# moshimoshi-audio-v2.net
KiCad netlist of a schematic drawn in EAGLE
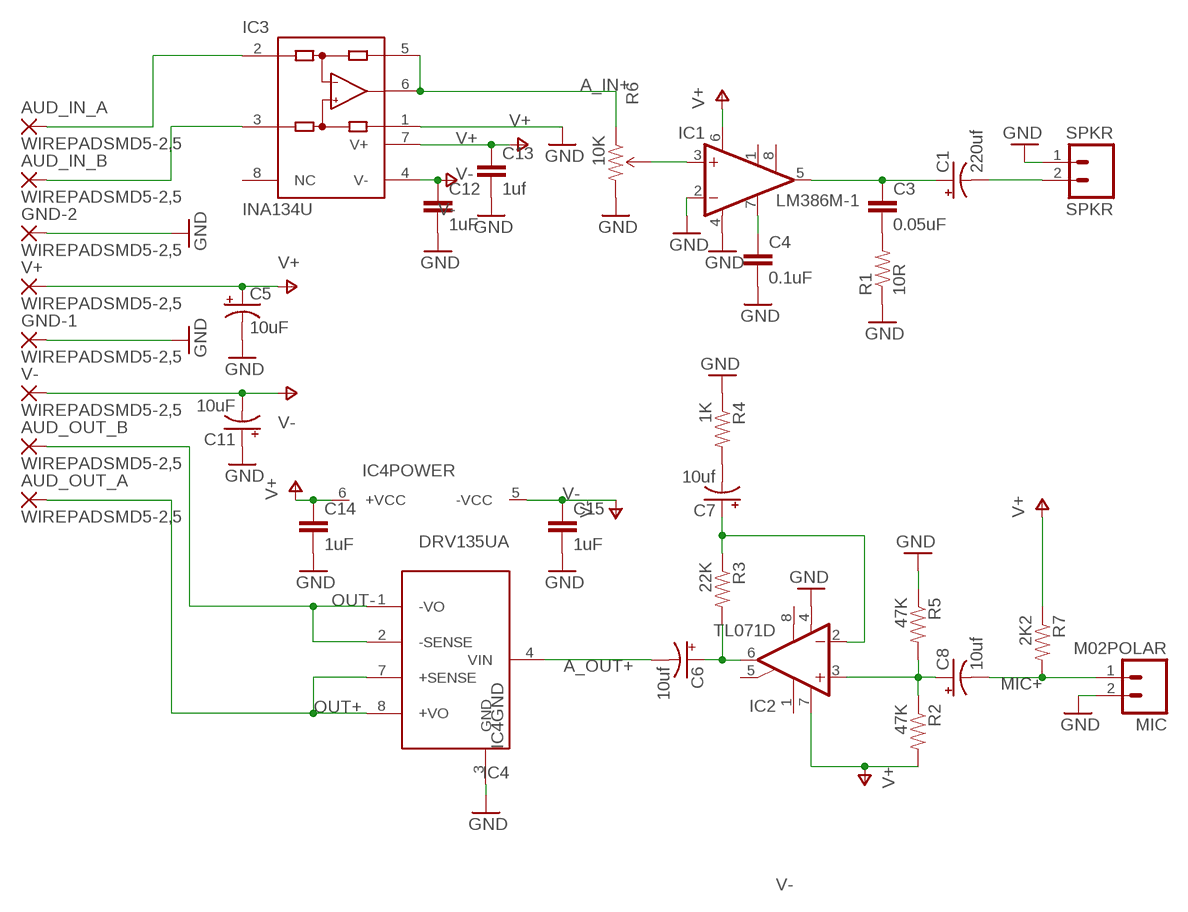
[diagram p0: schematic, sheet 1]

(export (version "E")
  (design (tool "Eeschema 10.0.6"))
  (components
    (comp (ref "AUD_IN_A")
      (value "WIREPADSMD5-2,5")
      (footprint "eagle-import:5-2,5")
      (libsource (lib "eagle-import") (part "WIREPADSMD5-2,5"))
    )
    (comp (ref "AUD_IN_B")
      (value "WIREPADSMD5-2,5")
      (footprint "eagle-import:5-2,5")
      (libsource (lib "eagle-import") (part "WIREPADSMD5-2,5"))
    )
    (comp (ref "AUD_OUT_A")
      (value "WIREPADSMD5-2,5")
      (footprint "eagle-import:5-2,5")
      (libsource (lib "eagle-import") (part "WIREPADSMD5-2,5"))
    )
    (comp (ref "AUD_OUT_B")
      (value "WIREPADSMD5-2,5")
      (footprint "eagle-import:5-2,5")
      (libsource (lib "eagle-import") (part "WIREPADSMD5-2,5"))
    )
    (comp (ref "C1")
      (value "220uf")
      (footprint "eagle-import:CPOL-RADIAL-100UF-25V")
      (libsource (lib "eagle-import") (part "CAP_POLPTH1"))
    )
    (comp (ref "C3")
      (value "0.05uF")
      (footprint "eagle-import:0805")
      (libsource (lib "eagle-import") (part "CAP0805"))
    )
    (comp (ref "C4")
      (value "0.1uF")
      (footprint "eagle-import:0603-CAP")
      (libsource (lib "eagle-import") (part "CAP0603-CAP"))
    )
    (comp (ref "C5")
      (value "10uF")
      (footprint "eagle-import:EIA3216")
      (libsource (lib "eagle-import") (part "10UF-16V-10%(TANT)"))
    )
    (comp (ref "C6")
      (value "10uf")
      (footprint "eagle-import:CPOL-RADIAL-10UF-25V")
      (libsource (lib "eagle-import") (part "CAP_POLPTH2"))
    )
    (comp (ref "C7")
      (value "10uf")
      (footprint "eagle-import:CPOL-RADIAL-10UF-25V")
      (libsource (lib "eagle-import") (part "CAP_POLPTH2"))
    )
    (comp (ref "C8")
      (value "10uf")
      (footprint "eagle-import:CPOL-RADIAL-10UF-25V")
      (libsource (lib "eagle-import") (part "CAP_POLPTH2"))
    )
    (comp (ref "C11")
      (value "10uF")
      (footprint "eagle-import:EIA3216")
      (libsource (lib "eagle-import") (part "10UF-16V-10%(TANT)"))
    )
    (comp (ref "C12")
      (value "1uF")
      (footprint "eagle-import:0805")
      (libsource (lib "eagle-import") (part "CAP0805"))
    )
    (comp (ref "C13")
      (value "1uf")
      (footprint "eagle-import:0805")
      (libsource (lib "eagle-import") (part "CAP0805"))
    )
    (comp (ref "C14")
      (value "1uF")
      (footprint "eagle-import:0805")
      (libsource (lib "eagle-import") (part "CAP0805"))
    )
    (comp (ref "C15")
      (value "1uF")
      (footprint "eagle-import:0805")
      (libsource (lib "eagle-import") (part "CAP0805"))
    )
    (comp (ref "GND-1")
      (value "WIREPADSMD5-2,5")
      (footprint "eagle-import:5-2,5")
      (libsource (lib "eagle-import") (part "WIREPADSMD5-2,5"))
    )
    (comp (ref "GND-2")
      (value "WIREPADSMD5-2,5")
      (footprint "eagle-import:5-2,5")
      (libsource (lib "eagle-import") (part "WIREPADSMD5-2,5"))
    )
    (comp (ref "IC1")
      (value "LM386M-1")
      (footprint "eagle-import:SO08")
      (libsource (lib "eagle-import") (part "LM386?-M1"))
    )
    (comp (ref "IC2")
      (value "TL071D")
      (footprint "eagle-import:SO08")
      (libsource (lib "eagle-import") (part "TL071D"))
    )
    (comp (ref "IC3")
      (value "INA134U")
      (footprint "eagle-import:SO08")
      (fields (field (name "MPN") "INA134UAE4"))
      (libsource (lib "eagle-import") (part "INA134U"))
    )
    (comp (ref "IC4")
      (value "DRV135UA")
      (footprint "eagle-import:SO08")
      (libsource (lib "eagle-import") (part "DRV135UA"))
    )
    (comp (ref "MIC")
      (value "M02POLAR")
      (footprint "eagle-import:MOLEX-1X2")
      (libsource (lib "eagle-import") (part "M02POLAR"))
    )
    (comp (ref "R1")
      (value "10R")
      (footprint "eagle-import:0805")
      (libsource (lib "eagle-import") (part "RESISTOR0805-RES"))
    )
    (comp (ref "R2")
      (value "47K")
      (footprint "eagle-import:0603-RES")
      (libsource (lib "eagle-import") (part "RESISTOR0603-RES"))
    )
    (comp (ref "R3")
      (value "22K")
      (footprint "eagle-import:0603-RES")
      (libsource (lib "eagle-import") (part "RESISTOR0603-RES"))
    )
    (comp (ref "R4")
      (value "1K")
      (footprint "eagle-import:0603-RES")
      (libsource (lib "eagle-import") (part "RESISTOR0603-RES"))
    )
    (comp (ref "R5")
      (value "47K")
      (footprint "eagle-import:0603-RES")
      (libsource (lib "eagle-import") (part "RESISTOR0603-RES"))
    )
    (comp (ref "R6")
      (value "10K")
      (footprint "eagle-import:TRIMPOT-3MM-2")
      (libsource (lib "eagle-import") (part "TRIMPOT3MM-2"))
    )
    (comp (ref "R7")
      (value "2K2")
      (footprint "eagle-import:0603-RES")
      (libsource (lib "eagle-import") (part "RESISTOR0603-RES"))
    )
    (comp (ref "SPKR")
      (value "SPKR")
      (footprint "eagle-import:MOLEX-1X2")
      (libsource (lib "eagle-import") (part "M02POLAR"))
    )
    (comp (ref "V+")
      (value "WIREPADSMD5-2,5")
      (footprint "eagle-import:5-2,5")
      (libsource (lib "eagle-import") (part "WIREPADSMD5-2,5"))
    )
    (comp (ref "V-")
      (value "WIREPADSMD5-2,5")
      (footprint "eagle-import:5-2,5")
      (libsource (lib "eagle-import") (part "WIREPADSMD5-2,5"))
    )
  )
  (nets
    (net (code "1") (name "/A_IN+") (class "Default")
      (node (ref "IC3") (pin "5") (pinfunction "SENSE_5") (pintype "passive"))
      (node (ref "IC3") (pin "6") (pinfunction "OUT_6") (pintype "output"))
      (node (ref "R6") (pin "1") (pinfunction "CCW_1") (pintype "passive"))
    )
    (net (code "2") (name "/A_OUT+") (class "Default")
      (node (ref "C6") (pin "2") (pinfunction "-_2") (pintype "passive"))
      (node (ref "IC4") (pin "4") (pinfunction "VIN_4") (pintype "bidirectional"))
    )
    (net (code "3") (name "/MIC+") (class "Default")
      (node (ref "C8") (pin "2") (pinfunction "-_2") (pintype "passive"))
      (node (ref "MIC") (pin "1") (pinfunction "1_1") (pintype "passive"))
      (node (ref "R7") (pin "2") (pinfunction "2_2") (pintype "passive"))
    )
    (net (code "4") (name "/OUT+") (class "Default")
      (node (ref "AUD_OUT_A") (pin "1") (pinfunction "P_1") (pintype "passive"))
      (node (ref "IC4") (pin "7") (pinfunction "+SENSE_7") (pintype "bidirectional"))
      (node (ref "IC4") (pin "8") (pinfunction "+VO_8") (pintype "bidirectional"))
    )
    (net (code "5") (name "/OUT-") (class "Default")
      (node (ref "AUD_OUT_B") (pin "1") (pinfunction "P_1") (pintype "passive"))
      (node (ref "IC4") (pin "1") (pinfunction "-VO_1") (pintype "bidirectional"))
      (node (ref "IC4") (pin "2") (pinfunction "-SENSE_2") (pintype "bidirectional"))
    )
    (net (code "6") (name "GND") (class "Default")
      (node (ref "C11") (pin "A") (pinfunction "+_A") (pintype "passive"))
      (node (ref "C12") (pin "2") (pinfunction "2_2") (pintype "passive"))
      (node (ref "C13") (pin "2") (pinfunction "2_2") (pintype "passive"))
      (node (ref "C14") (pin "2") (pinfunction "2_2") (pintype "passive"))
      (node (ref "C15") (pin "2") (pinfunction "2_2") (pintype "passive"))
      (node (ref "C4") (pin "2") (pinfunction "2_2") (pintype "passive"))
      (node (ref "C5") (pin "C") (pinfunction "-_C") (pintype "passive"))
      (node (ref "GND-1") (pin "1") (pinfunction "P_1") (pintype "passive"))
      (node (ref "GND-2") (pin "1") (pinfunction "P_1") (pintype "passive"))
      (node (ref "IC1") (pin "2") (pinfunction "-IN_2") (pintype "input"))
      (node (ref "IC1") (pin "4") (pinfunction "GND_4") (pintype "power_in"))
      (node (ref "IC2") (pin "4") (pinfunction "V-_4") (pintype "power_in"))
      (node (ref "IC3") (pin "1") (pinfunction "REF_1") (pintype "passive"))
      (node (ref "IC4") (pin "3") (pinfunction "GND_3") (pintype "power_in"))
      (node (ref "MIC") (pin "2") (pinfunction "2_2") (pintype "passive"))
      (node (ref "R1") (pin "1") (pinfunction "1_1") (pintype "passive"))
      (node (ref "R4") (pin "1") (pinfunction "1_1") (pintype "passive"))
      (node (ref "R5") (pin "1") (pinfunction "1_1") (pintype "passive"))
      (node (ref "R6") (pin "3") (pinfunction "CW_3") (pintype "passive"))
      (node (ref "SPKR") (pin "1") (pinfunction "1_1") (pintype "passive"))
    )
    (net (code "7") (name "Net-(AUD_IN_A-P)") (class "Default")
      (node (ref "AUD_IN_A") (pin "1") (pinfunction "P_1") (pintype "passive"))
      (node (ref "IC3") (pin "2") (pinfunction "-IN_2") (pintype "input"))
    )
    (net (code "8") (name "Net-(AUD_IN_B-P)") (class "Default")
      (node (ref "AUD_IN_B") (pin "1") (pinfunction "P_1") (pintype "passive"))
      (node (ref "IC3") (pin "3") (pinfunction "+IN_3") (pintype "input"))
    )
    (net (code "9") (name "Net-(C1-+)") (class "Default")
      (node (ref "C1") (pin "1") (pinfunction "+_1") (pintype "passive"))
      (node (ref "C3") (pin "1") (pinfunction "1_1") (pintype "passive"))
      (node (ref "IC1") (pin "5") (pinfunction "OUT_5") (pintype "output"))
    )
    (net (code "10") (name "Net-(C1--)") (class "Default")
      (node (ref "C1") (pin "2") (pinfunction "-_2") (pintype "passive"))
      (node (ref "SPKR") (pin "2") (pinfunction "2_2") (pintype "passive"))
    )
    (net (code "11") (name "Net-(C3-Pad2)") (class "Default")
      (node (ref "C3") (pin "2") (pinfunction "2_2") (pintype "passive"))
      (node (ref "R1") (pin "2") (pinfunction "2_2") (pintype "passive"))
    )
    (net (code "12") (name "Net-(C6-+)") (class "Default")
      (node (ref "C6") (pin "1") (pinfunction "+_1") (pintype "passive"))
      (node (ref "IC2") (pin "6") (pinfunction "OUT_6") (pintype "output"))
      (node (ref "R3") (pin "2") (pinfunction "2_2") (pintype "passive"))
    )
    (net (code "13") (name "Net-(C7-+)") (class "Default")
      (node (ref "C7") (pin "1") (pinfunction "+_1") (pintype "passive"))
      (node (ref "IC2") (pin "2") (pinfunction "-IN_2") (pintype "input"))
      (node (ref "R3") (pin "1") (pinfunction "1_1") (pintype "passive"))
    )
    (net (code "14") (name "Net-(C7--)") (class "Default")
      (node (ref "C7") (pin "2") (pinfunction "-_2") (pintype "passive"))
      (node (ref "R4") (pin "2") (pinfunction "2_2") (pintype "passive"))
    )
    (net (code "15") (name "Net-(C8-+)") (class "Default")
      (node (ref "C8") (pin "1") (pinfunction "+_1") (pintype "passive"))
      (node (ref "IC2") (pin "3") (pinfunction "+IN_3") (pintype "input"))
      (node (ref "R2") (pin "1") (pinfunction "1_1") (pintype "passive"))
      (node (ref "R5") (pin "2") (pinfunction "2_2") (pintype "passive"))
    )
    (net (code "16") (name "Net-(IC1-+IN)") (class "Default")
      (node (ref "IC1") (pin "3") (pinfunction "+IN_3") (pintype "input"))
      (node (ref "R6") (pin "2") (pinfunction "WIPER_2") (pintype "passive"))
    )
    (net (code "17") (name "Net-(IC1-BYPASS)") (class "Default")
      (node (ref "C4") (pin "1") (pinfunction "1_1") (pintype "passive"))
      (node (ref "IC1") (pin "7") (pinfunction "BYPASS_7") (pintype "passive"))
    )
    (net (code "18") (name "V+") (class "Default")
      (node (ref "C13") (pin "1") (pinfunction "1_1") (pintype "passive"))
      (node (ref "C14") (pin "1") (pinfunction "1_1") (pintype "passive"))
      (node (ref "C5") (pin "A") (pinfunction "+_A") (pintype "passive"))
      (node (ref "IC1") (pin "6") (pinfunction "VS_6") (pintype "power_in"))
      (node (ref "IC2") (pin "7") (pinfunction "V+_7") (pintype "power_in"))
      (node (ref "IC3") (pin "7") (pinfunction "V+_7") (pintype "power_in"))
      (node (ref "IC4") (pin "6") (pinfunction "+VCC_6") (pintype "power_in"))
      (node (ref "R2") (pin "2") (pinfunction "2_2") (pintype "passive"))
      (node (ref "R7") (pin "1") (pinfunction "1_1") (pintype "passive"))
      (node (ref "V+") (pin "1") (pinfunction "P_1") (pintype "passive"))
    )
    (net (code "19") (name "V-") (class "Default")
      (node (ref "C11") (pin "C") (pinfunction "-_C") (pintype "passive"))
      (node (ref "C12") (pin "1") (pinfunction "1_1") (pintype "passive"))
      (node (ref "C15") (pin "1") (pinfunction "1_1") (pintype "passive"))
      (node (ref "IC3") (pin "4") (pinfunction "V-_4") (pintype "power_in"))
      (node (ref "IC4") (pin "5") (pinfunction "-VCC_5") (pintype "power_in"))
      (node (ref "V-") (pin "1") (pinfunction "P_1") (pintype "passive"))
    )
    (net (code "20") (name "unconnected-(IC1-GAIN-Pad1)") (class "Default")
      (node (ref "IC1") (pin "1") (pinfunction "GAIN_1") (pintype "passive"))
    )
    (net (code "21") (name "unconnected-(IC1-GAIN-Pad8)") (class "Default")
      (node (ref "IC1") (pin "8") (pinfunction "GAIN_8") (pintype "passive"))
    )
    (net (code "22") (name "unconnected-(IC2-ON1-Pad1)") (class "Default")
      (node (ref "IC2") (pin "1") (pinfunction "ON1_1") (pintype "passive"))
    )
    (net (code "23") (name "unconnected-(IC2-ON2-Pad5)") (class "Default")
      (node (ref "IC2") (pin "5") (pinfunction "ON2_5") (pintype "passive"))
    )
    (net (code "24") (name "unconnected-(IC2-OPT-Pad8)") (class "Default")
      (node (ref "IC2") (pin "8") (pinfunction "OPT_8") (pintype "passive"))
    )
    (net (code "25") (name "unconnected-(IC3-NC-Pad8)") (class "Default")
      (node (ref "IC3") (pin "8") (pinfunction "NC_8") (pintype "no_connect"))
    )
  )
)
